# USB-RS485.net
KiCad netlist of a schematic drawn in Altium Designer
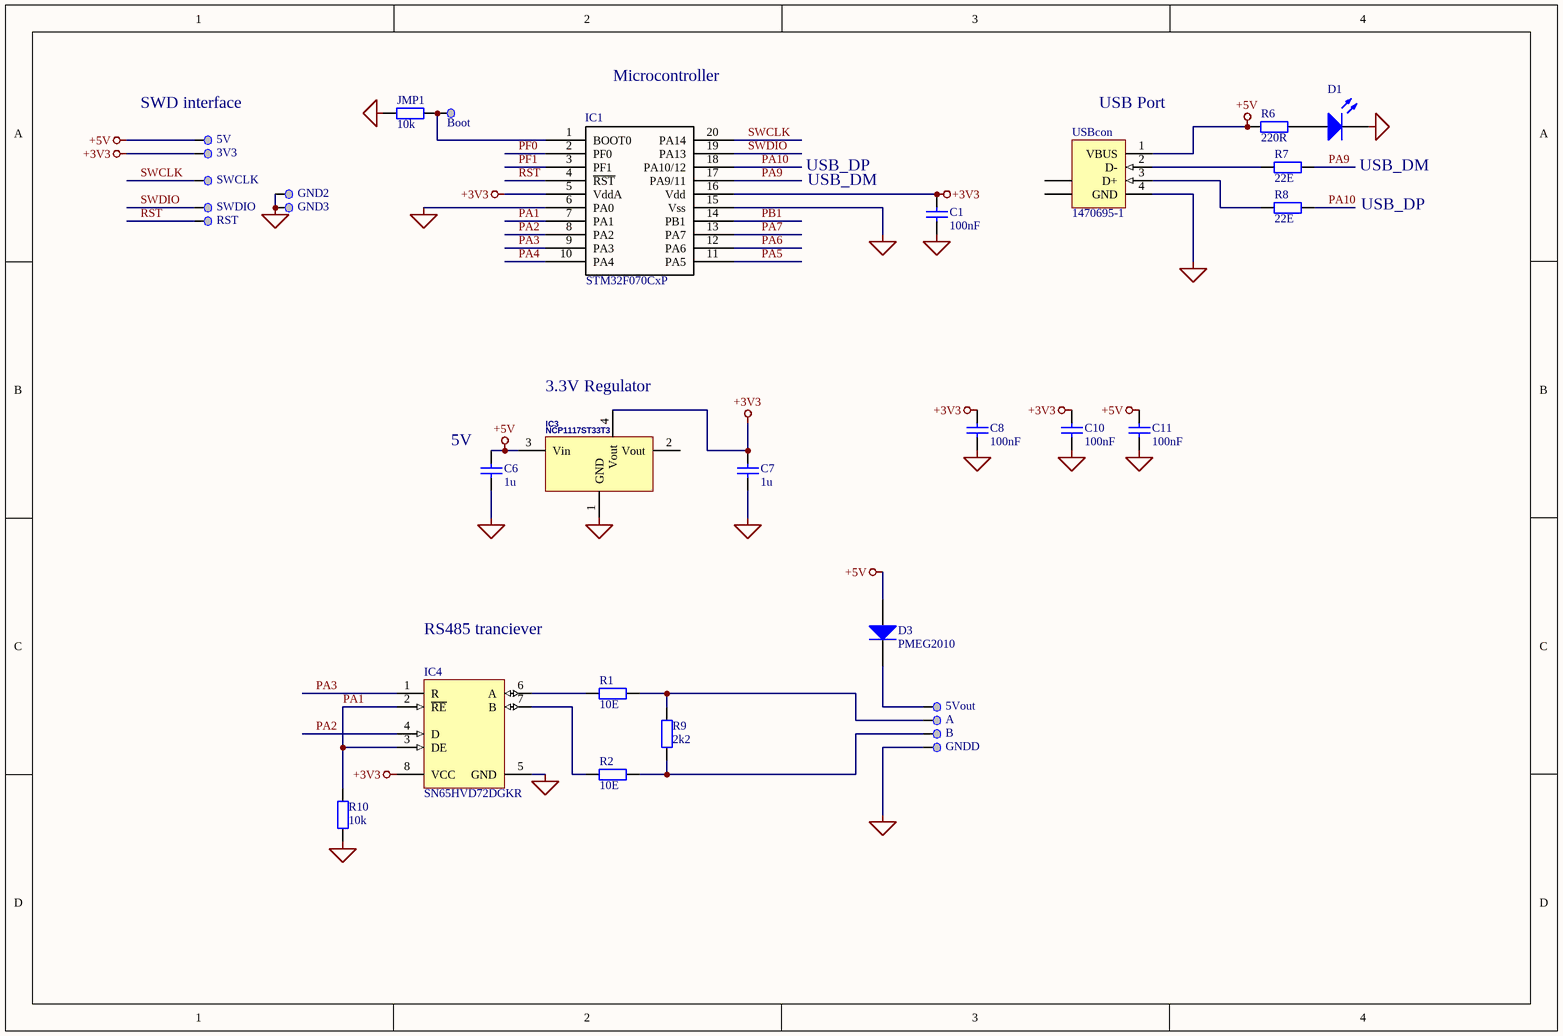
[diagram p0: USB-RS485.SchDoc]

(export (version "E")
  (design (tool "Eeschema 10.0.6"))
  (components
    (comp (ref "3V3") (value "~") (footprint "En_pin_TP") (libsource (lib "moja") (part "En_pin")))
    (comp (ref "5V") (value "~") (footprint "En_pin_TP") (libsource (lib "moja") (part "En_pin")))
    (comp (ref "5Vout") (value "~") (footprint "En_pin_TP") (libsource (lib "moja") (part "En_pin")))
    (comp (ref "A") (value "~") (footprint "En_pin_TP") (libsource (lib "moja") (part "En_pin")))
    (comp (ref "B") (value "~") (footprint "En_pin_TP") (libsource (lib "moja") (part "En_pin")))
    (comp (ref "Boot") (value "~") (footprint "En_pin_TP") (libsource (lib "moja") (part "En_pin")))
    (comp (ref "C1")
      (value "100nF")
      (description "Capacitor")
      (fields (field (name "PUBLISHER") "Altium Limited"))
      (libsource (lib "Miscellaneous Devices") (part "Cap"))
    )
    (comp (ref "C6")
      (value "1u")
      (footprint "0603")
      (description "Capacitor")
      (fields (field (name "PUBLISHER") "Altium Limited"))
      (libsource (lib "Miscellaneous Devices") (part "Cap"))
    )
    (comp (ref "C7")
      (value "1u")
      (footprint "0603")
      (description "Capacitor")
      (fields (field (name "PUBLISHER") "Altium Limited"))
      (libsource (lib "Miscellaneous Devices") (part "Cap"))
    )
    (comp (ref "C8")
      (value "100nF")
      (description "Capacitor")
      (fields (field (name "PUBLISHER") "Altium Limited"))
      (libsource (lib "Miscellaneous Devices") (part "Cap"))
    )
    (comp (ref "C10")
      (value "100nF")
      (description "Capacitor")
      (fields (field (name "PUBLISHER") "Altium Limited"))
      (libsource (lib "Miscellaneous Devices") (part "Cap"))
    )
    (comp (ref "C11")
      (value "100nF")
      (description "Capacitor")
      (fields (field (name "PUBLISHER") "Altium Limited"))
      (libsource (lib "Miscellaneous Devices") (part "Cap"))
    )
    (comp (ref "D1")
      (value "LED3")
      (description "Typical BLUE SiC LED")
      (fields (field (name "PUBLISHER") "Altium Limited"))
      (libsource (lib "Miscellaneous Devices") (part "LED3"))
    )
    (comp (ref "D3")
      (value "PMEG2010")
      (footprint "SOD323")
      (description "1 Amp General Purpose Rectifier")
      (fields (field (name "PUBLISHER") "Altium Limited"))
      (libsource (lib "Miscellaneous Devices") (part "Diode 1N4007"))
    )
    (comp (ref "GND2") (value "~") (footprint "En_pin_TP") (libsource (lib "moja") (part "En_pin")))
    (comp (ref "GND3") (value "~") (footprint "En_pin_TP") (libsource (lib "moja") (part "En_pin")))
    (comp (ref "GNDD") (value "~") (footprint "En_pin_TP") (libsource (lib "moja") (part "En_pin")))
    (comp (ref "IC1")
      (value "STM32F070CxP")
      (footprint "TSOP65P640X110_HS-20N")
      (libsource (lib "moja") (part "STM32F070CxP"))
    )
    (comp (ref "IC3")
      (value "NCP1117ST33T3")
      (footprint "SOT223_M")
      (libsource (lib "*") (part "VOLTREG_LD1117S33"))
    )
    (comp (ref "IC4")
      (value "SN65HVD72DGKR")
      (footprint "DGK8_L")
      (fields (field (name "MANUFACTURER") "Texas Instruments") (field (name "PARTNUMBER") "SN65HVD20PE4"))
      (libsource (lib "Texas Instruments Interface RS-485") (part "SN65HVD20PE4"))
    )
    (comp (ref "JMP1")
      (value "10k")
      (footprint "0603")
      (description "Resistor")
      (fields (field (name "Comment") "Res2") (field (name "PUBLISHER") "Altium Limited"))
      (libsource (lib "") (part "Res2_2"))
    )
    (comp (ref "R1")
      (value "10E")
      (footprint "0603")
      (description "Resistor")
      (fields (field (name "Comment") "Res2") (field (name "PUBLISHER") "Altium Limited"))
      (libsource (lib "Miscellaneous Devices") (part "Res2"))
    )
    (comp (ref "R2")
      (value "10E")
      (footprint "0603")
      (description "Resistor")
      (fields (field (name "Comment") "Res2") (field (name "PUBLISHER") "Altium Limited"))
      (libsource (lib "Miscellaneous Devices") (part "Res2"))
    )
    (comp (ref "R6")
      (value "220R")
      (footprint "0603")
      (description "Resistor")
      (fields (field (name "Comment") "Res2") (field (name "PUBLISHER") "Altium Limited"))
      (libsource (lib "Miscellaneous Devices") (part "Res2"))
    )
    (comp (ref "R7")
      (value "22E")
      (footprint "0603")
      (description "Resistor")
      (fields (field (name "Comment") "Res2") (field (name "PUBLISHER") "Altium Limited"))
      (libsource (lib "Miscellaneous Devices") (part "Res2"))
    )
    (comp (ref "R8")
      (value "22E")
      (footprint "0603")
      (description "Resistor")
      (fields (field (name "Comment") "Res2") (field (name "PUBLISHER") "Altium Limited"))
      (libsource (lib "Miscellaneous Devices") (part "Res2"))
    )
    (comp (ref "R9")
      (value "2k2")
      (footprint "0603")
      (description "Resistor")
      (fields (field (name "Comment") "Res2") (field (name "PUBLISHER") "Altium Limited"))
      (libsource (lib "") (part "Res2_1"))
    )
    (comp (ref "R10")
      (value "10k")
      (footprint "0603")
      (description "Resistor")
      (fields (field (name "Comment") "Res2") (field (name "PUBLISHER") "Altium Limited"))
      (libsource (lib "") (part "Res2_1"))
    )
    (comp (ref "RST") (value "~") (footprint "En_pin_TP") (libsource (lib "moja") (part "En_pin")))
    (comp (ref "SWCLK") (value "~") (footprint "En_pin_TP") (libsource (lib "moja") (part "En_pin")))
    (comp (ref "SWDIO") (value "~") (footprint "En_pin_TP") (libsource (lib "moja") (part "En_pin")))
    (comp (ref "USBcon")
      (value "1470695-1")
      (footprint "1470695")
      (description "USB 1.1, Right Angle, SMT, A Type, Plug, 4 Position, Natural")
      (fields (field (name "PUBLISHER") "Altium Limited"))
      (libsource (lib "AMP Serial Bus USB") (part "1470695-1"))
    )
  )
  (nets
    (net (code "1") (name "+3V3") (class "Default")
      (node (ref "3V3") (pin "1") (pinfunction "1_1") (pintype "passive"))
      (node (ref "C1") (pin "1") (pinfunction "1_1") (pintype "passive"))
      (node (ref "C10") (pin "1") (pinfunction "1_1") (pintype "passive"))
      (node (ref "C7") (pin "1") (pinfunction "1_1") (pintype "passive"))
      (node (ref "C8") (pin "1") (pinfunction "1_1") (pintype "passive"))
      (node (ref "IC1") (pin "16") (pinfunction "Vdd_16") (pintype "passive"))
      (node (ref "IC1") (pin "5") (pinfunction "VddA_5") (pintype "passive"))
      (node (ref "IC3") (pin "4") (pinfunction "Vout_4") (pintype "passive"))
      (node (ref "IC4") (pin "8") (pinfunction "VCC_8") (pintype "power_in"))
    )
    (net (code "2") (name "+5V") (class "Default")
      (node (ref "5V") (pin "1") (pinfunction "1_1") (pintype "passive"))
      (node (ref "C11") (pin "1") (pinfunction "1_1") (pintype "passive"))
      (node (ref "C6") (pin "1") (pinfunction "1_1") (pintype "passive"))
      (node (ref "D3") (pin "1") (pinfunction "A_1") (pintype "passive"))
      (node (ref "IC3") (pin "3") (pinfunction "Vin_3") (pintype "passive"))
      (node (ref "R6") (pin "2") (pinfunction "2_2") (pintype "passive"))
      (node (ref "USBcon") (pin "1") (pinfunction "VBUS_1") (pintype "power_in"))
    )
    (net (code "3") (name "/PA1") (class "Default")
      (node (ref "IC1") (pin "7") (pinfunction "PA1_7") (pintype "passive"))
      (node (ref "IC4") (pin "2") (pinfunction "~{RE}_2") (pintype "input"))
      (node (ref "IC4") (pin "3") (pinfunction "DE_3") (pintype "input"))
      (node (ref "R10") (pin "1") (pinfunction "1_1") (pintype "passive"))
    )
    (net (code "4") (name "/PA2") (class "Default")
      (node (ref "IC1") (pin "8") (pinfunction "PA2_8") (pintype "passive"))
      (node (ref "IC4") (pin "4") (pinfunction "D_4") (pintype "input"))
    )
    (net (code "5") (name "/PA3") (class "Default")
      (node (ref "IC1") (pin "9") (pinfunction "PA3_9") (pintype "passive"))
      (node (ref "IC4") (pin "1") (pinfunction "R_1") (pintype "tri_state"))
    )
    (net (code "6") (name "/PA4") (class "Default")
      (node (ref "IC1") (pin "10") (pinfunction "PA4_10") (pintype "passive"))
    )
    (net (code "7") (name "/PA5") (class "Default")
      (node (ref "IC1") (pin "11") (pinfunction "PA5_11") (pintype "passive"))
    )
    (net (code "8") (name "/PA6") (class "Default")
      (node (ref "IC1") (pin "12") (pinfunction "PA6_12") (pintype "passive"))
    )
    (net (code "9") (name "/PA7") (class "Default")
      (node (ref "IC1") (pin "13") (pinfunction "PA7_13") (pintype "passive"))
    )
    (net (code "10") (name "/PA9") (class "Default")
      (node (ref "IC1") (pin "17") (pinfunction "PA9/11_17") (pintype "passive"))
      (node (ref "R7") (pin "1") (pinfunction "1_1") (pintype "passive"))
    )
    (net (code "11") (name "/PA10") (class "Default")
      (node (ref "IC1") (pin "18") (pinfunction "PA10/12_18") (pintype "passive"))
      (node (ref "R8") (pin "1") (pinfunction "1_1") (pintype "passive"))
    )
    (net (code "12") (name "/PB1") (class "Default")
      (node (ref "IC1") (pin "14") (pinfunction "PB1_14") (pintype "passive"))
    )
    (net (code "13") (name "/PF0") (class "Default")
      (node (ref "IC1") (pin "2") (pinfunction "PF0_2") (pintype "passive"))
    )
    (net (code "14") (name "/PF1") (class "Default")
      (node (ref "IC1") (pin "3") (pinfunction "PF1_3") (pintype "passive"))
    )
    (net (code "15") (name "/RST") (class "Default")
      (node (ref "IC1") (pin "4") (pinfunction "~{RST}_4") (pintype "passive"))
      (node (ref "RST") (pin "1") (pinfunction "1_1") (pintype "passive"))
    )
    (net (code "16") (name "/SWCLK") (class "Default")
      (node (ref "IC1") (pin "20") (pinfunction "PA14_20") (pintype "passive"))
      (node (ref "SWCLK") (pin "1") (pinfunction "1_1") (pintype "passive"))
    )
    (net (code "17") (name "/SWDIO") (class "Default")
      (node (ref "IC1") (pin "19") (pinfunction "PA13_19") (pintype "passive"))
      (node (ref "SWDIO") (pin "1") (pinfunction "1_1") (pintype "passive"))
    )
    (net (code "18") (name "Net-(A-Pad1)") (class "Default")
      (node (ref "A") (pin "1") (pinfunction "1_1") (pintype "passive"))
      (node (ref "R1") (pin "1") (pinfunction "1_1") (pintype "passive"))
      (node (ref "R9") (pin "1") (pinfunction "1_1") (pintype "passive"))
    )
    (net (code "19") (name "Net-(B-Pad1)") (class "Default")
      (node (ref "B") (pin "1") (pinfunction "1_1") (pintype "passive"))
      (node (ref "R2") (pin "1") (pinfunction "1_1") (pintype "passive"))
      (node (ref "R9") (pin "2") (pinfunction "2_2") (pintype "passive"))
    )
    (net (code "20") (name "Net-(D1-A)") (class "Default")
      (node (ref "D1") (pin "1") (pinfunction "A_1") (pintype "passive"))
      (node (ref "R6") (pin "1") (pinfunction "1_1") (pintype "passive"))
    )
    (net (code "21") (name "Net-(D3-K)") (class "Default")
      (node (ref "5Vout") (pin "1") (pinfunction "1_1") (pintype "passive"))
      (node (ref "D3") (pin "2") (pinfunction "K_2") (pintype "passive"))
    )
    (net (code "22") (name "Net-(IC1-BOOT0)") (class "Default")
      (node (ref "Boot") (pin "1") (pinfunction "1_1") (pintype "passive"))
      (node (ref "IC1") (pin "1") (pinfunction "BOOT0_1") (pintype "passive"))
      (node (ref "JMP1") (pin "2") (pinfunction "2_2") (pintype "passive"))
    )
    (net (code "23") (name "Net-(IC4-A)") (class "Default")
      (node (ref "IC4") (pin "6") (pinfunction "A_6") (pintype "bidirectional"))
      (node (ref "R1") (pin "2") (pinfunction "2_2") (pintype "passive"))
    )
    (net (code "24") (name "Net-(IC4-B)") (class "Default")
      (node (ref "IC4") (pin "7") (pinfunction "B_7") (pintype "bidirectional"))
      (node (ref "R2") (pin "2") (pinfunction "2_2") (pintype "passive"))
    )
    (net (code "25") (name "Net-(USBcon-D+)") (class "Default")
      (node (ref "R8") (pin "2") (pinfunction "2_2") (pintype "passive"))
      (node (ref "USBcon") (pin "3") (pinfunction "D+_3") (pintype "input"))
    )
    (net (code "26") (name "Net-(USBcon-D-)") (class "Default")
      (node (ref "R7") (pin "2") (pinfunction "2_2") (pintype "passive"))
      (node (ref "USBcon") (pin "2") (pinfunction "D-_2") (pintype "input"))
    )
    (net (code "27") (name "SGND") (class "Default")
      (node (ref "C1") (pin "2") (pinfunction "2_2") (pintype "passive"))
      (node (ref "C10") (pin "2") (pinfunction "2_2") (pintype "passive"))
      (node (ref "C11") (pin "2") (pinfunction "2_2") (pintype "passive"))
      (node (ref "C6") (pin "2") (pinfunction "2_2") (pintype "passive"))
      (node (ref "C7") (pin "2") (pinfunction "2_2") (pintype "passive"))
      (node (ref "C8") (pin "2") (pinfunction "2_2") (pintype "passive"))
      (node (ref "D1") (pin "2") (pinfunction "K_2") (pintype "passive"))
      (node (ref "GND2") (pin "1") (pinfunction "1_1") (pintype "passive"))
      (node (ref "GND3") (pin "1") (pinfunction "1_1") (pintype "passive"))
      (node (ref "GNDD") (pin "1") (pinfunction "1_1") (pintype "passive"))
      (node (ref "IC1") (pin "15") (pinfunction "Vss_15") (pintype "passive"))
      (node (ref "IC1") (pin "6") (pinfunction "PA0_6") (pintype "passive"))
      (node (ref "IC3") (pin "1") (pinfunction "GND_1") (pintype "passive"))
      (node (ref "IC4") (pin "5") (pinfunction "GND_5") (pintype "power_in"))
      (node (ref "JMP1") (pin "1") (pinfunction "1_1") (pintype "passive"))
      (node (ref "R10") (pin "2") (pinfunction "2_2") (pintype "passive"))
      (node (ref "USBcon") (pin "4") (pinfunction "GND_4") (pintype "power_in"))
    )
    (net (code "28") (name "unconnected-(IC3-Vout-Pad2)") (class "Default")
      (node (ref "IC3") (pin "2") (pinfunction "Vout_2") (pintype "passive"))
    )
    (net (code "29") (name "unconnected-(USBcon-SHLD-Pad5)") (class "Default")
      (node (ref "USBcon") (pin "5") (pinfunction "SHLD_5") (pintype "passive"))
    )
    (net (code "30") (name "unconnected-(USBcon-SHLD-Pad6)") (class "Default")
      (node (ref "USBcon") (pin "6") (pinfunction "SHLD_6") (pintype "passive"))
    )
  )
)
